# SCH_Pico-slide-show-2_2025-07-07.net
KiCad netlist of a schematic drawn in EasyEDA
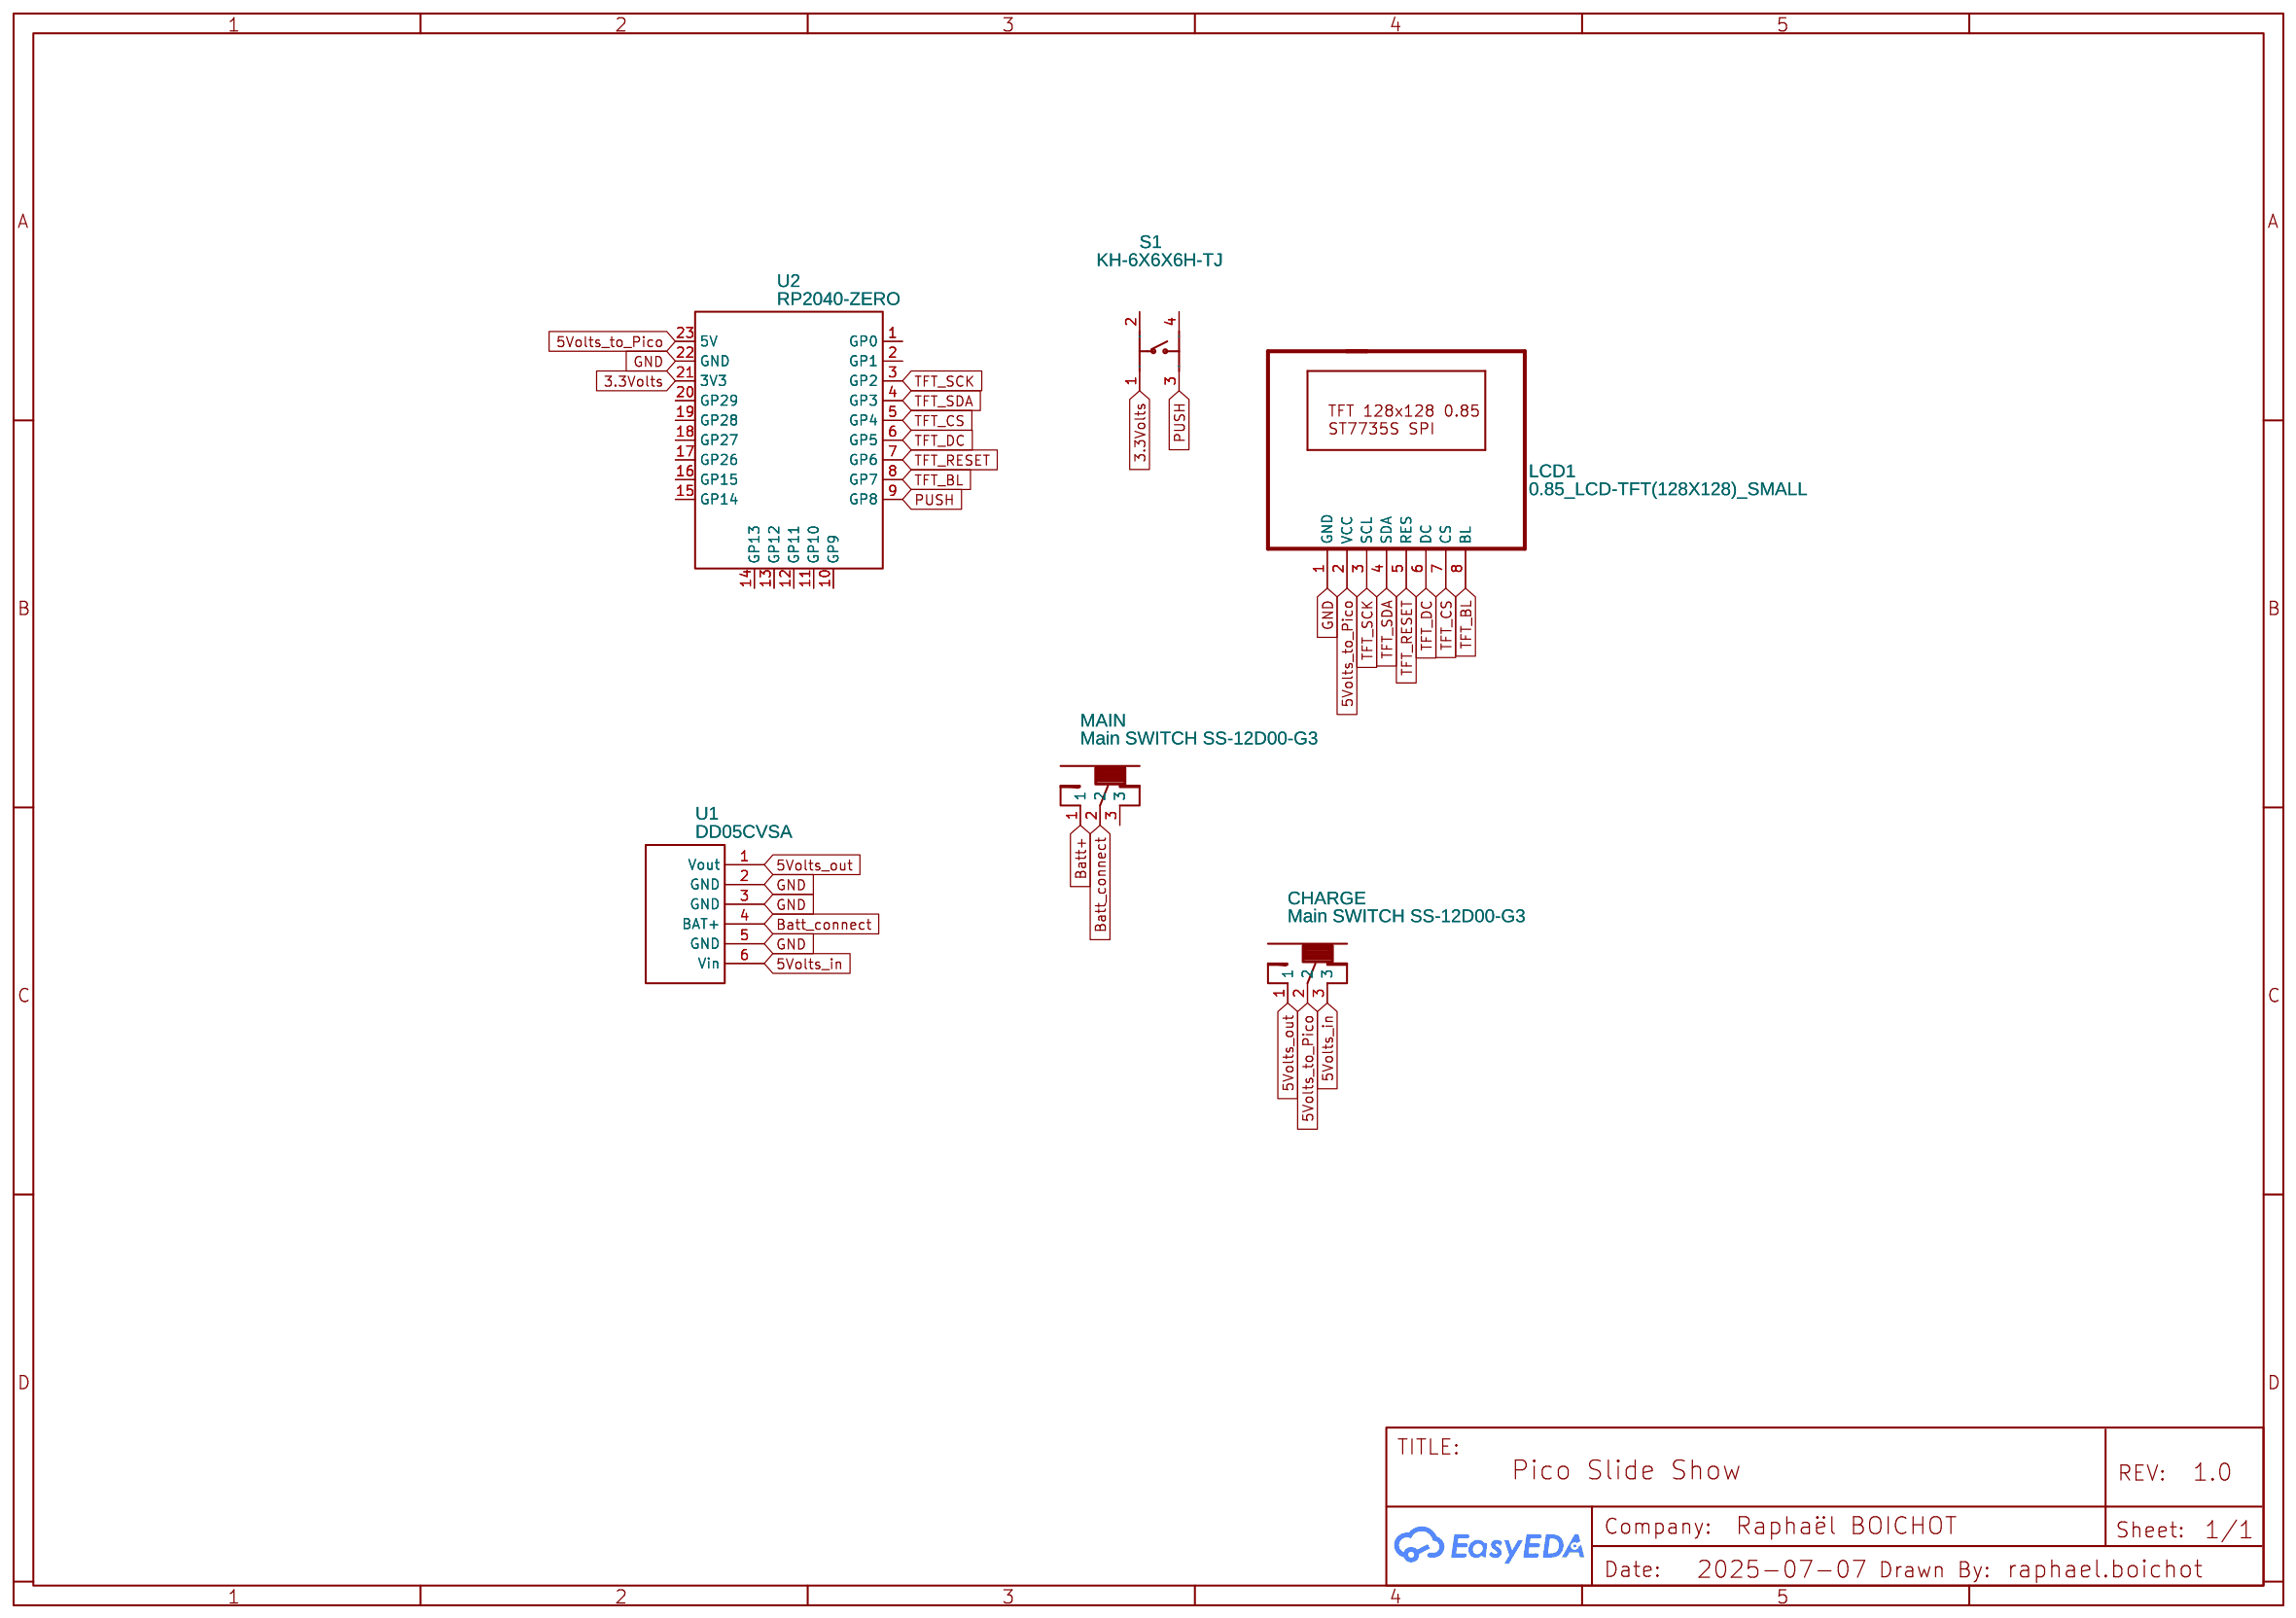
[diagram p0: schematic sheet]

(export (version "E")
  (design (tool "Eeschema 10.0.6"))
  (components
    (comp (ref "CHARGE")
      (value "Main SWITCH SS-12D00-G3")
      (fields
        (field (name "Manufacturer Part") "TOGGLE SWITCH SS-12D00-G3")
        (field (name "Manufacturer") "Dailywell")
      )
      (libsource (lib "") (part "TOGGLE SWITCH SS-12D00-G3_1"))
    )
    (comp (ref "LCD1")
      (value "0.85_LCD-TFT(128X128)_SMALL")
      (libsource (lib "") (part "1.44_LCD-TFT(128X128)_SMALL"))
    )
    (comp (ref "MAIN")
      (value "Main SWITCH SS-12D00-G3")
      (fields
        (field (name "Manufacturer Part") "TOGGLE SWITCH SS-12D00-G3")
        (field (name "Manufacturer") "Dailywell")
      )
      (libsource (lib "") (part "TOGGLE SWITCH SS-12D00-G3"))
    )
    (comp (ref "S1")
      (value "KH-6X6X6H-TJ")
      (fields (field (name "Manufacturer") "kinghelm(金航标)"))
      (libsource (lib "") (part "KH-6X6X6H-TJ"))
    )
    (comp (ref "U1") (value "DD05CVSA") (libsource (lib "") (part "DD05CVSA")))
    (comp (ref "U2") (value "RP2040-ZERO") (libsource (lib "") (part "RP2040-ZERO")))
  )
  (nets
    (net (code "1") (name "3.3Volts") (class "Default")
      (node (ref "S1") (pin "1") (pinfunction "1_1") (pintype "unspecified"))
      (node (ref "U2") (pin "21") (pinfunction "3V3_21") (pintype "unspecified"))
    )
    (net (code "2") (name "5Volts_in") (class "Default")
      (node (ref "CHARGE") (pin "3") (pinfunction "3_3") (pintype "unspecified"))
      (node (ref "U1") (pin "6") (pinfunction "Vin_6") (pintype "unspecified"))
    )
    (net (code "3") (name "5Volts_out") (class "Default")
      (node (ref "CHARGE") (pin "1") (pinfunction "1_1") (pintype "bidirectional"))
      (node (ref "U1") (pin "1") (pinfunction "Vout_1") (pintype "unspecified"))
    )
    (net (code "4") (name "5Volts_to_Pico") (class "Default")
      (node (ref "CHARGE") (pin "2") (pinfunction "2_2") (pintype "bidirectional"))
      (node (ref "LCD1") (pin "2") (pinfunction "VCC_2") (pintype "output"))
      (node (ref "U2") (pin "23") (pinfunction "5V_23") (pintype "unspecified"))
    )
    (net (code "5") (name "Batt+") (class "Default")
      (node (ref "MAIN") (pin "1") (pinfunction "1_1") (pintype "bidirectional"))
    )
    (net (code "6") (name "Batt_connect") (class "Default")
      (node (ref "MAIN") (pin "2") (pinfunction "2_2") (pintype "bidirectional"))
      (node (ref "U1") (pin "4") (pinfunction "BAT+_4") (pintype "unspecified"))
    )
    (net (code "7") (name "GND") (class "Default")
      (node (ref "LCD1") (pin "1") (pinfunction "GND_1") (pintype "passive"))
      (node (ref "U1") (pin "2") (pinfunction "GND_2") (pintype "unspecified"))
      (node (ref "U1") (pin "3") (pinfunction "GND_3") (pintype "unspecified"))
      (node (ref "U1") (pin "5") (pinfunction "GND_5") (pintype "unspecified"))
      (node (ref "U2") (pin "22") (pinfunction "GND_22") (pintype "unspecified"))
    )
    (net (code "8") (name "PUSH") (class "Default")
      (node (ref "S1") (pin "3") (pinfunction "3_3") (pintype "unspecified"))
      (node (ref "U2") (pin "9") (pinfunction "GP8_9") (pintype "unspecified"))
    )
    (net (code "9") (name "TFT_BL") (class "Default")
      (node (ref "LCD1") (pin "8") (pinfunction "BL_8") (pintype "input"))
      (node (ref "U2") (pin "8") (pinfunction "GP7_8") (pintype "unspecified"))
    )
    (net (code "10") (name "TFT_CS") (class "Default")
      (node (ref "LCD1") (pin "7") (pinfunction "CS_7") (pintype "unspecified"))
      (node (ref "U2") (pin "5") (pinfunction "GP4_5") (pintype "unspecified"))
    )
    (net (code "11") (name "TFT_DC") (class "Default")
      (node (ref "LCD1") (pin "6") (pinfunction "DC_6") (pintype "input"))
      (node (ref "U2") (pin "6") (pinfunction "GP5_6") (pintype "unspecified"))
    )
    (net (code "12") (name "TFT_RESET") (class "Default")
      (node (ref "LCD1") (pin "5") (pinfunction "RES_5") (pintype "input"))
      (node (ref "U2") (pin "7") (pinfunction "GP6_7") (pintype "unspecified"))
    )
    (net (code "13") (name "TFT_SCK") (class "Default")
      (node (ref "LCD1") (pin "3") (pinfunction "SCL_3") (pintype "input"))
      (node (ref "U2") (pin "3") (pinfunction "GP2_3") (pintype "unspecified"))
    )
    (net (code "14") (name "TFT_SDA") (class "Default")
      (node (ref "LCD1") (pin "4") (pinfunction "SDA_4") (pintype "input"))
      (node (ref "U2") (pin "4") (pinfunction "GP3_4") (pintype "unspecified"))
    )
    (net (code "15") (name "unconnected-(MAIN-Pad3)") (class "Default")
      (node (ref "MAIN") (pin "3") (pinfunction "3_3") (pintype "unspecified"))
    )
    (net (code "16") (name "unconnected-(S1-Pad2)") (class "Default")
      (node (ref "S1") (pin "2") (pinfunction "2_2") (pintype "unspecified"))
    )
    (net (code "17") (name "unconnected-(S1-Pad4)") (class "Default")
      (node (ref "S1") (pin "4") (pinfunction "4_4") (pintype "unspecified"))
    )
    (net (code "18") (name "unconnected-(U2-GP0-Pad1)") (class "Default")
      (node (ref "U2") (pin "1") (pinfunction "GP0_1") (pintype "unspecified"))
    )
    (net (code "19") (name "unconnected-(U2-GP1-Pad2)") (class "Default")
      (node (ref "U2") (pin "2") (pinfunction "GP1_2") (pintype "unspecified"))
    )
    (net (code "20") (name "unconnected-(U2-GP9-Pad10)") (class "Default")
      (node (ref "U2") (pin "10") (pinfunction "GP9_10") (pintype "unspecified"))
    )
    (net (code "21") (name "unconnected-(U2-GP10-Pad11)") (class "Default")
      (node (ref "U2") (pin "11") (pinfunction "GP10_11") (pintype "unspecified"))
    )
    (net (code "22") (name "unconnected-(U2-GP11-Pad12)") (class "Default")
      (node (ref "U2") (pin "12") (pinfunction "GP11_12") (pintype "unspecified"))
    )
    (net (code "23") (name "unconnected-(U2-GP12-Pad13)") (class "Default")
      (node (ref "U2") (pin "13") (pinfunction "GP12_13") (pintype "unspecified"))
    )
    (net (code "24") (name "unconnected-(U2-GP13-Pad14)") (class "Default")
      (node (ref "U2") (pin "14") (pinfunction "GP13_14") (pintype "unspecified"))
    )
    (net (code "25") (name "unconnected-(U2-GP14-Pad15)") (class "Default")
      (node (ref "U2") (pin "15") (pinfunction "GP14_15") (pintype "unspecified"))
    )
    (net (code "26") (name "unconnected-(U2-GP15-Pad16)") (class "Default")
      (node (ref "U2") (pin "16") (pinfunction "GP15_16") (pintype "unspecified"))
    )
    (net (code "27") (name "unconnected-(U2-GP26-Pad17)") (class "Default")
      (node (ref "U2") (pin "17") (pinfunction "GP26_17") (pintype "unspecified"))
    )
    (net (code "28") (name "unconnected-(U2-GP27-Pad18)") (class "Default")
      (node (ref "U2") (pin "18") (pinfunction "GP27_18") (pintype "unspecified"))
    )
    (net (code "29") (name "unconnected-(U2-GP28-Pad19)") (class "Default")
      (node (ref "U2") (pin "19") (pinfunction "GP28_19") (pintype "unspecified"))
    )
    (net (code "30") (name "unconnected-(U2-GP29-Pad20)") (class "Default")
      (node (ref "U2") (pin "20") (pinfunction "GP29_20") (pintype "unspecified"))
    )
  )
)
